# Input.net
KiCad netlist of a schematic drawn in Altium Designer
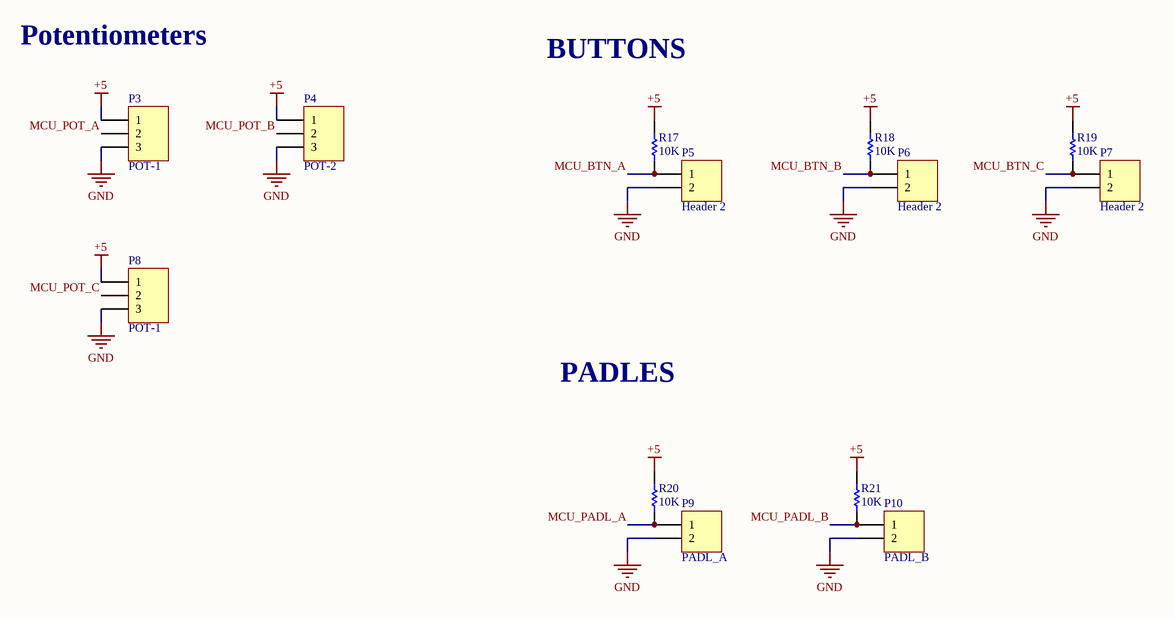
[diagram p0: Input.SchDoc]

(export (version "E")
  (design (tool "Eeschema 10.0.6"))
  (components
    (comp (ref "P3")
      (value "POT-1")
      (footprint "HDR1X3")
      (description "Header, 3-Pin")
      (fields (field (name "PUBLISHER") "Altium Limited"))
      (libsource (lib "Miscellaneous Connectors") (part "Header 3"))
    )
    (comp (ref "P4")
      (value "POT-2")
      (footprint "HDR1X3")
      (description "Header, 3-Pin")
      (fields (field (name "PUBLISHER") "Altium Limited"))
      (libsource (lib "Miscellaneous Connectors") (part "Header 3"))
    )
    (comp (ref "P5")
      (value "Header 2")
      (footprint "HDR1X2")
      (description "Header, 2-Pin")
      (fields (field (name "PUBLISHER") "Altium Limited"))
      (libsource (lib "Miscellaneous Connectors") (part "Header 2"))
    )
    (comp (ref "P6")
      (value "Header 2")
      (footprint "HDR1X2")
      (description "Header, 2-Pin")
      (fields (field (name "PUBLISHER") "Altium Limited"))
      (libsource (lib "Miscellaneous Connectors") (part "Header 2"))
    )
    (comp (ref "P7")
      (value "Header 2")
      (footprint "HDR1X2")
      (description "Header, 2-Pin")
      (fields (field (name "PUBLISHER") "Altium Limited"))
      (libsource (lib "Miscellaneous Connectors") (part "Header 2"))
    )
    (comp (ref "P8")
      (value "POT-1")
      (footprint "HDR1X3")
      (description "Header, 3-Pin")
      (fields (field (name "PUBLISHER") "Altium Limited"))
      (libsource (lib "Miscellaneous Connectors") (part "Header 3"))
    )
    (comp (ref "P9")
      (value "PADL_A")
      (footprint "HDR1X2")
      (description "Header, 2-Pin")
      (fields (field (name "PUBLISHER") "Altium Limited"))
      (libsource (lib "Miscellaneous Connectors") (part "Header 2"))
    )
    (comp (ref "P10")
      (value "PADL_B")
      (footprint "HDR1X2")
      (description "Header, 2-Pin")
      (fields (field (name "PUBLISHER") "Altium Limited"))
      (libsource (lib "Miscellaneous Connectors") (part "Header 2"))
    )
    (comp (ref "R17")
      (value "10K")
      (footprint "RESC0603(1608)_N")
      (description "10K 0.1W 5% 0603 (1608 Metric)  SMD")
      (fields (field (name "TOLERANCE") "5 %") (field (name "POWER") "0.1 W"))
      (libsource (lib "Altium Content Vault") (part "RES"))
    )
    (comp (ref "R18")
      (value "10K")
      (footprint "RESC0603(1608)_N")
      (description "10K 0.1W 5% 0603 (1608 Metric)  SMD")
      (fields (field (name "TOLERANCE") "5 %") (field (name "POWER") "0.1 W"))
      (libsource (lib "Altium Content Vault") (part "RES"))
    )
    (comp (ref "R19")
      (value "10K")
      (footprint "RESC0603(1608)_N")
      (description "10K 0.1W 5% 0603 (1608 Metric)  SMD")
      (fields (field (name "TOLERANCE") "5 %") (field (name "POWER") "0.1 W"))
      (libsource (lib "Altium Content Vault") (part "RES"))
    )
    (comp (ref "R20")
      (value "10K")
      (footprint "RESC0603(1608)_N")
      (description "10K 0.1W 5% 0603 (1608 Metric)  SMD")
      (fields (field (name "TOLERANCE") "5 %") (field (name "POWER") "0.1 W"))
      (libsource (lib "Altium Content Vault") (part "RES"))
    )
    (comp (ref "R21")
      (value "10K")
      (footprint "RESC0603(1608)_N")
      (description "10K 0.1W 5% 0603 (1608 Metric)  SMD")
      (fields (field (name "TOLERANCE") "5 %") (field (name "POWER") "0.1 W"))
      (libsource (lib "Altium Content Vault") (part "RES"))
    )
  )
  (nets
    (net (code "1") (name "+5") (class "Default")
      (node (ref "P3") (pin "1") (pinfunction "1_1") (pintype "passive"))
      (node (ref "P4") (pin "1") (pinfunction "1_1") (pintype "passive"))
      (node (ref "P8") (pin "1") (pinfunction "1_1") (pintype "passive"))
      (node (ref "R17") (pin "1") (pinfunction "1_1") (pintype "passive"))
      (node (ref "R18") (pin "1") (pinfunction "1_1") (pintype "passive"))
      (node (ref "R19") (pin "1") (pinfunction "1_1") (pintype "passive"))
      (node (ref "R20") (pin "1") (pinfunction "1_1") (pintype "passive"))
      (node (ref "R21") (pin "1") (pinfunction "1_1") (pintype "passive"))
    )
    (net (code "2") (name "/MCU_BTN_A") (class "Default")
      (node (ref "P5") (pin "1") (pinfunction "1_1") (pintype "passive"))
      (node (ref "R17") (pin "2") (pinfunction "2_2") (pintype "passive"))
    )
    (net (code "3") (name "/MCU_BTN_B") (class "Default")
      (node (ref "P6") (pin "1") (pinfunction "1_1") (pintype "passive"))
      (node (ref "R18") (pin "2") (pinfunction "2_2") (pintype "passive"))
    )
    (net (code "4") (name "/MCU_BTN_C") (class "Default")
      (node (ref "P7") (pin "1") (pinfunction "1_1") (pintype "passive"))
      (node (ref "R19") (pin "2") (pinfunction "2_2") (pintype "passive"))
    )
    (net (code "5") (name "/MCU_PADL_A") (class "Default")
      (node (ref "P9") (pin "1") (pinfunction "1_1") (pintype "passive"))
      (node (ref "R20") (pin "2") (pinfunction "2_2") (pintype "passive"))
    )
    (net (code "6") (name "/MCU_PADL_B") (class "Default")
      (node (ref "P10") (pin "1") (pinfunction "1_1") (pintype "passive"))
      (node (ref "R21") (pin "2") (pinfunction "2_2") (pintype "passive"))
    )
    (net (code "7") (name "/MCU_POT_A") (class "Default")
      (node (ref "P3") (pin "2") (pinfunction "2_2") (pintype "passive"))
    )
    (net (code "8") (name "/MCU_POT_B") (class "Default")
      (node (ref "P4") (pin "2") (pinfunction "2_2") (pintype "passive"))
    )
    (net (code "9") (name "/MCU_POT_C") (class "Default")
      (node (ref "P8") (pin "2") (pinfunction "2_2") (pintype "passive"))
    )
    (net (code "10") (name "GND") (class "Default")
      (node (ref "P10") (pin "2") (pinfunction "2_2") (pintype "passive"))
      (node (ref "P3") (pin "3") (pinfunction "3_3") (pintype "passive"))
      (node (ref "P4") (pin "3") (pinfunction "3_3") (pintype "passive"))
      (node (ref "P5") (pin "2") (pinfunction "2_2") (pintype "passive"))
      (node (ref "P6") (pin "2") (pinfunction "2_2") (pintype "passive"))
      (node (ref "P7") (pin "2") (pinfunction "2_2") (pintype "passive"))
      (node (ref "P8") (pin "3") (pinfunction "3_3") (pintype "passive"))
      (node (ref "P9") (pin "2") (pinfunction "2_2") (pintype "passive"))
    )
  )
)
